# Scope_ArduinoCurveTracerV10.net
KiCad netlist of a schematic drawn in EAGLE
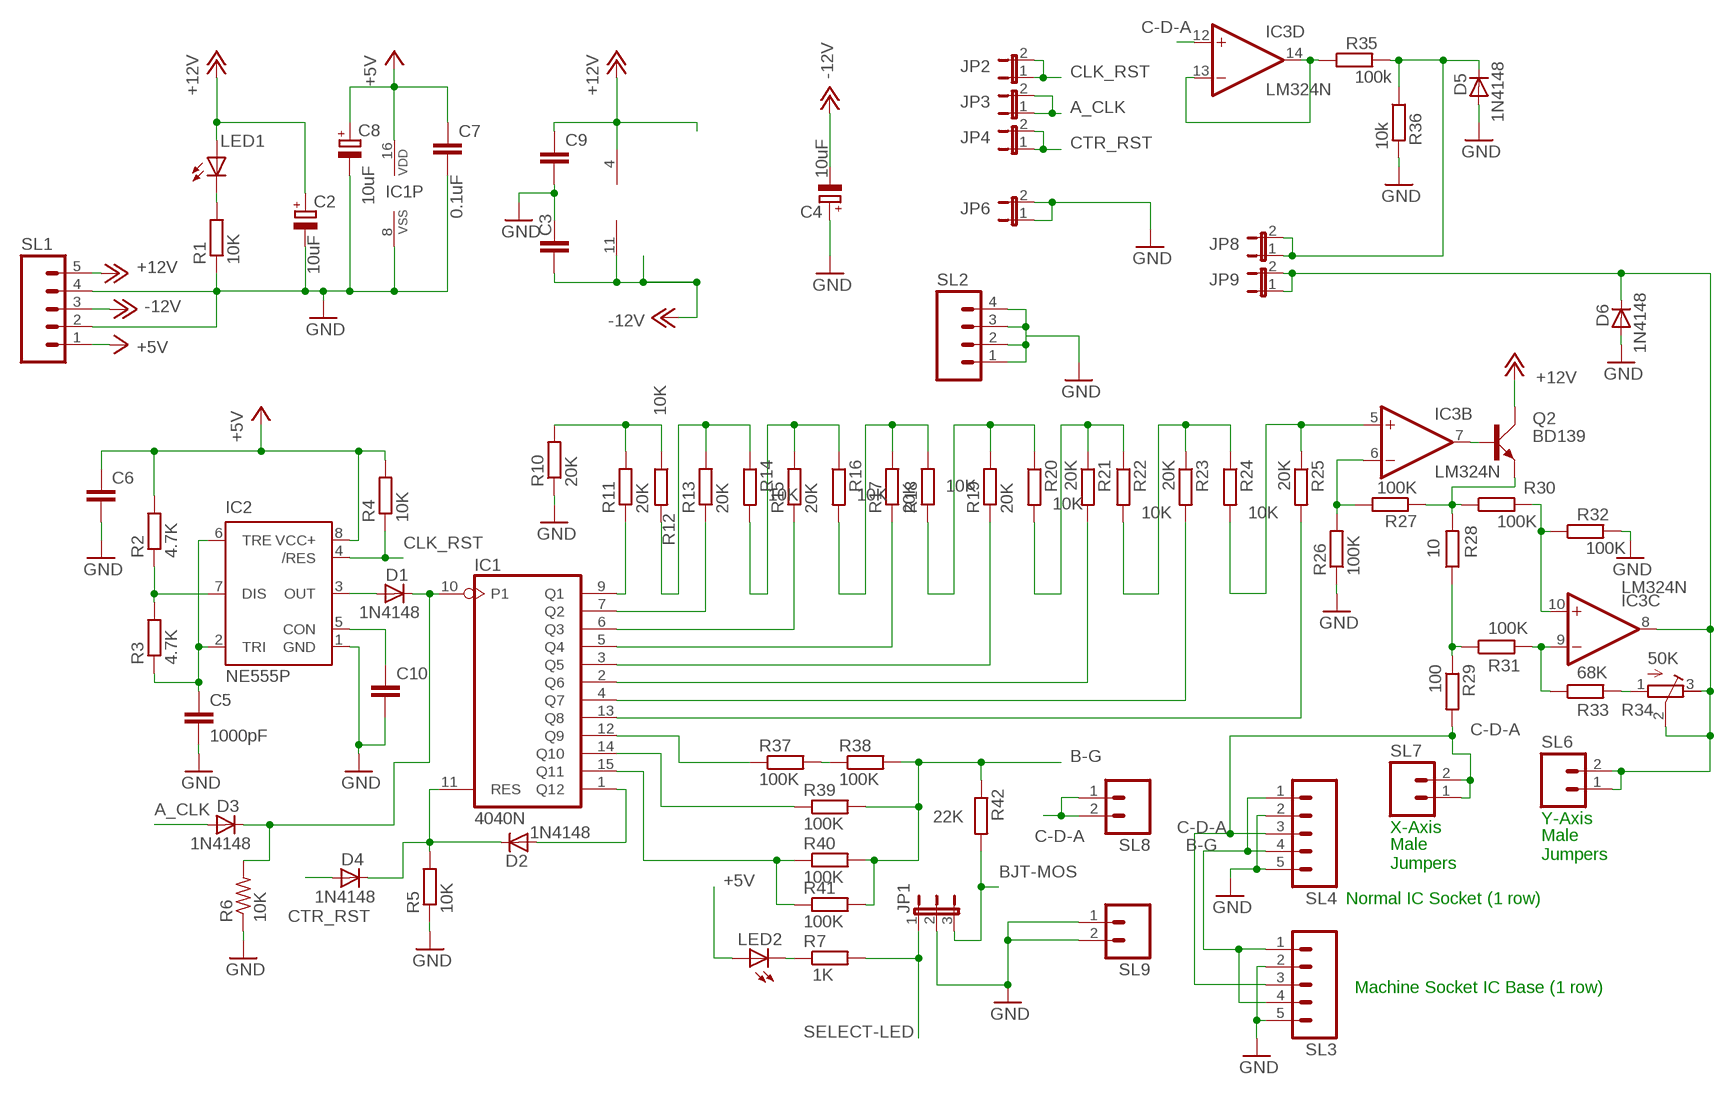
[diagram p0: schematic, sheet 1]

(export (version "E")
  (design (tool "Eeschema 10.0.6"))
  (components
    (comp (ref "C2")
      (value "10uF")
      (footprint "eagle-import:E2-5")
      (libsource (lib "eagle-import") (part "CPOL-EUE2-5"))
    )
    (comp (ref "C3")
      (value "0.1uF")
      (footprint "eagle-import:C025-024X044")
      (libsource (lib "eagle-import") (part "C-EU025-024X044"))
    )
    (comp (ref "C4")
      (value "10uF")
      (footprint "eagle-import:E2-5")
      (libsource (lib "eagle-import") (part "CPOL-EUE2-5"))
    )
    (comp (ref "C5")
      (value "1000pF")
      (footprint "eagle-import:C025-025X050")
      (libsource (lib "eagle-import") (part "C-EU025-025X050"))
    )
    (comp (ref "C6")
      (value "0.1uF")
      (footprint "eagle-import:C025-024X044")
      (libsource (lib "eagle-import") (part "C-EU025-024X044"))
    )
    (comp (ref "C7")
      (value "0.1uF")
      (footprint "eagle-import:C025-024X044")
      (libsource (lib "eagle-import") (part "C-EU025-024X044"))
    )
    (comp (ref "C8")
      (value "10uF")
      (footprint "eagle-import:E2-5")
      (libsource (lib "eagle-import") (part "CPOL-EUE2-5"))
    )
    (comp (ref "C9")
      (value "0.1uF")
      (footprint "eagle-import:C025-024X044")
      (libsource (lib "eagle-import") (part "C-EU025-024X044"))
    )
    (comp (ref "C10")
      (value "0.1uF")
      (footprint "eagle-import:C025-024X044")
      (libsource (lib "eagle-import") (part "C-EU025-024X044"))
    )
    (comp (ref "D1")
      (value "1N4148")
      (footprint "eagle-import:DO35-7")
      (libsource (lib "eagle-import") (part "1N4148DO35-7"))
    )
    (comp (ref "D2")
      (value "1N4148")
      (footprint "eagle-import:DO35-7")
      (libsource (lib "eagle-import") (part "1N4148DO35-7"))
    )
    (comp (ref "D3")
      (value "1N4148")
      (footprint "eagle-import:DO35-7")
      (libsource (lib "eagle-import") (part "1N4148DO35-7"))
    )
    (comp (ref "D4")
      (value "1N4148")
      (footprint "eagle-import:DO35-7")
      (libsource (lib "eagle-import") (part "1N4148DO35-7"))
    )
    (comp (ref "D5")
      (value "1N4148")
      (footprint "eagle-import:DO35-7")
      (libsource (lib "eagle-import") (part "1N4148DO35-7"))
    )
    (comp (ref "D6")
      (value "1N4148")
      (footprint "eagle-import:DO35-10")
      (libsource (lib "eagle-import") (part "1N4148DO35-10"))
    )
    (comp (ref "IC1")
      (value "4040N")
      (footprint "eagle-import:DIL16")
      (libsource (lib "eagle-import") (part "4040N"))
    )
    (comp (ref "IC2")
      (value "NE555P")
      (footprint "eagle-import:DIL-08")
      (fields (field (name "MF") "Arrow Electronics") (field (name "MPN") "NE555N"))
      (libsource (lib "eagle-import") (part "NE555P"))
    )
    (comp (ref "IC3")
      (value "LM324N")
      (footprint "eagle-import:DIL14")
      (libsource (lib "eagle-import") (part "LM324N"))
    )
    (comp (ref "JP1")
      (value "JP2E")
      (footprint "eagle-import:JP2")
      (libsource (lib "eagle-import") (part "JP2E"))
    )
    (comp (ref "JP2")
      (value "JP1E")
      (footprint "eagle-import:JP1")
      (libsource (lib "eagle-import") (part "JP1E"))
    )
    (comp (ref "JP3")
      (value "JP1E")
      (footprint "eagle-import:JP1")
      (libsource (lib "eagle-import") (part "JP1E"))
    )
    (comp (ref "JP4")
      (value "JP1E")
      (footprint "eagle-import:JP1")
      (libsource (lib "eagle-import") (part "JP1E"))
    )
    (comp (ref "JP6")
      (value "JP1E")
      (footprint "eagle-import:JP1")
      (libsource (lib "eagle-import") (part "JP1E"))
    )
    (comp (ref "JP8")
      (value "JP1E")
      (footprint "eagle-import:JP1")
      (libsource (lib "eagle-import") (part "JP1E"))
    )
    (comp (ref "JP9")
      (value "JP1E")
      (footprint "eagle-import:JP1")
      (libsource (lib "eagle-import") (part "JP1E"))
    )
    (comp (ref "LED1")
      (value "LED3MM")
      (footprint "eagle-import:LED3MM")
      (libsource (lib "eagle-import") (part "LED3MM"))
    )
    (comp (ref "LED2")
      (value "LED3MM")
      (footprint "eagle-import:LED3MM")
      (libsource (lib "eagle-import") (part "LED3MM"))
    )
    (comp (ref "Q2")
      (value "BD139")
      (footprint "eagle-import:TO126AV")
      (libsource (lib "eagle-import") (part "BD139"))
    )
    (comp (ref "R1")
      (value "10K")
      (footprint "eagle-import:0204_7")
      (libsource (lib "eagle-import") (part "R-EU_0204/7"))
    )
    (comp (ref "R2")
      (value "4.7K")
      (footprint "eagle-import:0204_7")
      (libsource (lib "eagle-import") (part "R-EU_0204/7"))
    )
    (comp (ref "R3")
      (value "4.7K")
      (footprint "eagle-import:0204_7")
      (libsource (lib "eagle-import") (part "R-EU_0204/7"))
    )
    (comp (ref "R4")
      (value "10K")
      (footprint "eagle-import:0204_7")
      (libsource (lib "eagle-import") (part "R-EU_0204/7"))
    )
    (comp (ref "R5")
      (value "10K")
      (footprint "eagle-import:0204_7")
      (libsource (lib "eagle-import") (part "R-EU_0204/7"))
    )
    (comp (ref "R6")
      (value "10K")
      (footprint "eagle-import:0204_7")
      (libsource (lib "eagle-import") (part "R-US_0204/7"))
    )
    (comp (ref "R7")
      (value "1K")
      (footprint "eagle-import:0204_7")
      (libsource (lib "eagle-import") (part "R-EU_0204/7"))
    )
    (comp (ref "R10")
      (value "20K")
      (footprint "eagle-import:0204_7")
      (libsource (lib "eagle-import") (part "R-EU_0204/7"))
    )
    (comp (ref "R11")
      (value "20K")
      (footprint "eagle-import:0204_7")
      (libsource (lib "eagle-import") (part "R-EU_0204/7"))
    )
    (comp (ref "R12")
      (value "10K")
      (footprint "eagle-import:0204_7")
      (libsource (lib "eagle-import") (part "R-EU_0204/7"))
    )
    (comp (ref "R13")
      (value "20K")
      (footprint "eagle-import:0204_7")
      (libsource (lib "eagle-import") (part "R-EU_0204/7"))
    )
    (comp (ref "R14")
      (value "10K")
      (footprint "eagle-import:0204_7")
      (libsource (lib "eagle-import") (part "R-EU_0204/7"))
    )
    (comp (ref "R15")
      (value "20K")
      (footprint "eagle-import:0204_7")
      (libsource (lib "eagle-import") (part "R-EU_0204/7"))
    )
    (comp (ref "R16")
      (value "10K")
      (footprint "eagle-import:0204_7")
      (libsource (lib "eagle-import") (part "R-EU_0204/7"))
    )
    (comp (ref "R17")
      (value "20K")
      (footprint "eagle-import:0204_7")
      (libsource (lib "eagle-import") (part "R-EU_0204/7"))
    )
    (comp (ref "R18")
      (value "10K")
      (footprint "eagle-import:0204_7")
      (libsource (lib "eagle-import") (part "R-EU_0204/7"))
    )
    (comp (ref "R19")
      (value "20K")
      (footprint "eagle-import:0204_7")
      (libsource (lib "eagle-import") (part "R-EU_0204/7"))
    )
    (comp (ref "R20")
      (value "10K")
      (footprint "eagle-import:0204_7")
      (libsource (lib "eagle-import") (part "R-EU_0204/7"))
    )
    (comp (ref "R21")
      (value "20K")
      (footprint "eagle-import:0204_7")
      (libsource (lib "eagle-import") (part "R-EU_0204/7"))
    )
    (comp (ref "R22")
      (value "10K")
      (footprint "eagle-import:0204_7")
      (libsource (lib "eagle-import") (part "R-EU_0204/7"))
    )
    (comp (ref "R23")
      (value "20K")
      (footprint "eagle-import:0204_7")
      (libsource (lib "eagle-import") (part "R-EU_0204/7"))
    )
    (comp (ref "R24")
      (value "10K")
      (footprint "eagle-import:0204_7")
      (libsource (lib "eagle-import") (part "R-EU_0204/7"))
    )
    (comp (ref "R25")
      (value "20K")
      (footprint "eagle-import:0204_7")
      (libsource (lib "eagle-import") (part "R-EU_0204/7"))
    )
    (comp (ref "R26")
      (value "100K")
      (footprint "eagle-import:0204_7")
      (libsource (lib "eagle-import") (part "R-EU_0204/7"))
    )
    (comp (ref "R27")
      (value "100K")
      (footprint "eagle-import:0204_7")
      (libsource (lib "eagle-import") (part "R-EU_0204/7"))
    )
    (comp (ref "R28")
      (value "10")
      (footprint "eagle-import:0207_10")
      (libsource (lib "eagle-import") (part "R-EU_0207/10"))
    )
    (comp (ref "R29")
      (value "100")
      (footprint "eagle-import:0309_12")
      (libsource (lib "eagle-import") (part "R-EU_0309/12"))
    )
    (comp (ref "R30")
      (value "100K")
      (footprint "eagle-import:0207_10")
      (libsource (lib "eagle-import") (part "R-EU_0207/10"))
    )
    (comp (ref "R31")
      (value "100K")
      (footprint "eagle-import:0204_7")
      (libsource (lib "eagle-import") (part "R-EU_0204/7"))
    )
    (comp (ref "R32")
      (value "100K")
      (footprint "eagle-import:0204_7")
      (libsource (lib "eagle-import") (part "R-EU_0204/7"))
    )
    (comp (ref "R33")
      (value "68K")
      (footprint "eagle-import:0204_7")
      (libsource (lib "eagle-import") (part "R-EU_0204/7"))
    )
    (comp (ref "R34")
      (value "50K")
      (footprint "eagle-import:RTRIM64W")
      (libsource (lib "eagle-import") (part "R-TRIMM64W"))
    )
    (comp (ref "R35")
      (value "100k")
      (footprint "eagle-import:0204_7")
      (libsource (lib "eagle-import") (part "R-EU_0204/7"))
    )
    (comp (ref "R36")
      (value "10k")
      (footprint "eagle-import:0204_7")
      (libsource (lib "eagle-import") (part "R-EU_0204/7"))
    )
    (comp (ref "R37")
      (value "100K")
      (footprint "eagle-import:0204_7")
      (libsource (lib "eagle-import") (part "R-EU_0204/7"))
    )
    (comp (ref "R38")
      (value "100K")
      (footprint "eagle-import:0204_7")
      (libsource (lib "eagle-import") (part "R-EU_0204/7"))
    )
    (comp (ref "R39")
      (value "100K")
      (footprint "eagle-import:0204_7")
      (libsource (lib "eagle-import") (part "R-EU_0204/7"))
    )
    (comp (ref "R40")
      (value "100K")
      (footprint "eagle-import:0204_7")
      (libsource (lib "eagle-import") (part "R-EU_0204/7"))
    )
    (comp (ref "R41")
      (value "100K")
      (footprint "eagle-import:0204_7")
      (libsource (lib "eagle-import") (part "R-EU_0204/7"))
    )
    (comp (ref "R42")
      (value "22K")
      (footprint "eagle-import:0204_7")
      (libsource (lib "eagle-import") (part "R-EU_0204/7"))
    )
    (comp (ref "SL1")
      (value "M05")
      (footprint "eagle-import:05P")
      (libsource (lib "eagle-import") (part "M05"))
    )
    (comp (ref "SL2")
      (value "M04")
      (footprint "eagle-import:04P")
      (libsource (lib "eagle-import") (part "M04"))
    )
    (comp (ref "SL3")
      (value "M05")
      (footprint "eagle-import:05P")
      (libsource (lib "eagle-import") (part "M05"))
    )
    (comp (ref "SL4")
      (value "M05")
      (footprint "eagle-import:05P")
      (libsource (lib "eagle-import") (part "M05"))
    )
    (comp (ref "SL6")
      (value "M02")
      (footprint "eagle-import:02P")
      (libsource (lib "eagle-import") (part "con-amp-quick_M02"))
    )
    (comp (ref "SL7")
      (value "M02")
      (footprint "eagle-import:02P")
      (libsource (lib "eagle-import") (part "M02"))
    )
    (comp (ref "SL8")
      (value "M02")
      (footprint "eagle-import:02P")
      (libsource (lib "eagle-import") (part "con-amp-quick_M02"))
    )
    (comp (ref "SL9")
      (value "M02")
      (footprint "eagle-import:02P")
      (libsource (lib "eagle-import") (part "con-amp-quick_M02"))
    )
  )
  (nets
    (net (code "1") (name "+5V") (class "Default")
      (node (ref "C6") (pin "1") (pinfunction "1_1") (pintype "passive"))
      (node (ref "C7") (pin "1") (pinfunction "1_1") (pintype "passive"))
      (node (ref "C8") (pin "+") (pinfunction "+_+") (pintype "passive"))
      (node (ref "IC1") (pin "16") (pinfunction "VDD_16") (pintype "power_in"))
      (node (ref "IC2") (pin "8") (pinfunction "VCC+_8") (pintype "power_in"))
      (node (ref "LED2") (pin "A") (pinfunction "A_A") (pintype "passive"))
      (node (ref "R2") (pin "2") (pinfunction "2_2") (pintype "passive"))
      (node (ref "R4") (pin "2") (pinfunction "2_2") (pintype "passive"))
      (node (ref "SL1") (pin "1") (pinfunction "1_1") (pintype "passive"))
    )
    (net (code "2") (name "+12V") (class "Default")
      (node (ref "C2") (pin "+") (pinfunction "+_+") (pintype "passive"))
      (node (ref "C9") (pin "1") (pinfunction "1_1") (pintype "passive"))
      (node (ref "IC3") (pin "4") (pinfunction "V+_4") (pintype "power_in"))
      (node (ref "LED1") (pin "A") (pinfunction "A_A") (pintype "passive"))
      (node (ref "Q2") (pin "C") (pinfunction "C_C") (pintype "passive"))
      (node (ref "SL1") (pin "5") (pinfunction "5_5") (pintype "passive"))
    )
    (net (code "3") (name "-12V") (class "Default")
      (node (ref "C3") (pin "2") (pinfunction "2_2") (pintype "passive"))
      (node (ref "C4") (pin "-") (pinfunction "-_-") (pintype "passive"))
      (node (ref "IC3") (pin "11") (pinfunction "V-_11") (pintype "power_in"))
      (node (ref "SL1") (pin "3") (pinfunction "3_3") (pintype "passive"))
    )
    (net (code "4") (name "/A_CLK") (class "Default")
      (node (ref "D3") (pin "A") (pinfunction "A_A") (pintype "passive"))
      (node (ref "JP3") (pin "1") (pinfunction "1_1") (pintype "passive"))
      (node (ref "JP3") (pin "2") (pinfunction "2_2") (pintype "passive"))
    )
    (net (code "5") (name "/B-G") (class "Default")
      (node (ref "R38") (pin "2") (pinfunction "2_2") (pintype "passive"))
      (node (ref "R39") (pin "2") (pinfunction "2_2") (pintype "passive"))
      (node (ref "R40") (pin "2") (pinfunction "2_2") (pintype "passive"))
      (node (ref "R41") (pin "2") (pinfunction "2_2") (pintype "passive"))
      (node (ref "R42") (pin "1") (pinfunction "1_1") (pintype "passive"))
      (node (ref "SL3") (pin "1") (pinfunction "1_1") (pintype "passive"))
      (node (ref "SL3") (pin "4") (pinfunction "4_4") (pintype "passive"))
      (node (ref "SL4") (pin "1") (pinfunction "1_1") (pintype "passive"))
      (node (ref "SL4") (pin "4") (pinfunction "4_4") (pintype "passive"))
    )
    (net (code "6") (name "/BJT-MOS") (class "Default")
      (node (ref "JP1") (pin "3") (pinfunction "3_3") (pintype "passive"))
      (node (ref "R42") (pin "2") (pinfunction "2_2") (pintype "passive"))
    )
    (net (code "7") (name "/C-D-A") (class "Default")
      (node (ref "IC3") (pin "12") (pinfunction "+IN_12") (pintype "input"))
      (node (ref "R29") (pin "2") (pinfunction "2_2") (pintype "passive"))
      (node (ref "SL3") (pin "3") (pinfunction "3_3") (pintype "passive"))
      (node (ref "SL4") (pin "3") (pinfunction "3_3") (pintype "passive"))
      (node (ref "SL7") (pin "1") (pinfunction "1_1") (pintype "passive"))
      (node (ref "SL7") (pin "2") (pinfunction "2_2") (pintype "passive"))
      (node (ref "SL8") (pin "1") (pinfunction "1_1") (pintype "passive"))
      (node (ref "SL8") (pin "2") (pinfunction "2_2") (pintype "passive"))
    )
    (net (code "8") (name "/CLK_RST") (class "Default")
      (node (ref "IC2") (pin "4") (pinfunction "/RES_4") (pintype "input"))
      (node (ref "JP2") (pin "1") (pinfunction "1_1") (pintype "passive"))
      (node (ref "JP2") (pin "2") (pinfunction "2_2") (pintype "passive"))
      (node (ref "R4") (pin "1") (pinfunction "1_1") (pintype "passive"))
    )
    (net (code "9") (name "/CTR_RST") (class "Default")
      (node (ref "D4") (pin "A") (pinfunction "A_A") (pintype "passive"))
      (node (ref "JP4") (pin "1") (pinfunction "1_1") (pintype "passive"))
      (node (ref "JP4") (pin "2") (pinfunction "2_2") (pintype "passive"))
    )
    (net (code "10") (name "/SELECT-LED") (class "Default")
      (node (ref "JP1") (pin "1") (pinfunction "1_1") (pintype "passive"))
      (node (ref "R7") (pin "2") (pinfunction "2_2") (pintype "passive"))
    )
    (net (code "11") (name "GND") (class "Default")
      (node (ref "C10") (pin "2") (pinfunction "2_2") (pintype "passive"))
      (node (ref "C2") (pin "-") (pinfunction "-_-") (pintype "passive"))
      (node (ref "C3") (pin "1") (pinfunction "1_1") (pintype "passive"))
      (node (ref "C4") (pin "+") (pinfunction "+_+") (pintype "passive"))
      (node (ref "C5") (pin "2") (pinfunction "2_2") (pintype "passive"))
      (node (ref "C6") (pin "2") (pinfunction "2_2") (pintype "passive"))
      (node (ref "C7") (pin "2") (pinfunction "2_2") (pintype "passive"))
      (node (ref "C8") (pin "-") (pinfunction "-_-") (pintype "passive"))
      (node (ref "C9") (pin "2") (pinfunction "2_2") (pintype "passive"))
      (node (ref "D5") (pin "A") (pinfunction "A_A") (pintype "passive"))
      (node (ref "D6") (pin "A") (pinfunction "A_A") (pintype "passive"))
      (node (ref "IC1") (pin "8") (pinfunction "VSS_8") (pintype "power_in"))
      (node (ref "IC2") (pin "1") (pinfunction "GND_1") (pintype "power_in"))
      (node (ref "JP1") (pin "2") (pinfunction "2_2") (pintype "passive"))
      (node (ref "JP6") (pin "1") (pinfunction "1_1") (pintype "passive"))
      (node (ref "JP6") (pin "2") (pinfunction "2_2") (pintype "passive"))
      (node (ref "R1") (pin "1") (pinfunction "1_1") (pintype "passive"))
      (node (ref "R10") (pin "1") (pinfunction "1_1") (pintype "passive"))
      (node (ref "R26") (pin "1") (pinfunction "1_1") (pintype "passive"))
      (node (ref "R32") (pin "2") (pinfunction "2_2") (pintype "passive"))
      (node (ref "R36") (pin "2") (pinfunction "2_2") (pintype "passive"))
      (node (ref "R5") (pin "1") (pinfunction "1_1") (pintype "passive"))
      (node (ref "R6") (pin "1") (pinfunction "1_1") (pintype "passive"))
      (node (ref "SL1") (pin "2") (pinfunction "2_2") (pintype "passive"))
      (node (ref "SL1") (pin "4") (pinfunction "4_4") (pintype "passive"))
      (node (ref "SL2") (pin "1") (pinfunction "1_1") (pintype "passive"))
      (node (ref "SL2") (pin "2") (pinfunction "2_2") (pintype "passive"))
      (node (ref "SL2") (pin "3") (pinfunction "3_3") (pintype "passive"))
      (node (ref "SL2") (pin "4") (pinfunction "4_4") (pintype "passive"))
      (node (ref "SL3") (pin "2") (pinfunction "2_2") (pintype "passive"))
      (node (ref "SL3") (pin "5") (pinfunction "5_5") (pintype "passive"))
      (node (ref "SL4") (pin "2") (pinfunction "2_2") (pintype "passive"))
      (node (ref "SL4") (pin "5") (pinfunction "5_5") (pintype "passive"))
      (node (ref "SL9") (pin "1") (pinfunction "1_1") (pintype "passive"))
      (node (ref "SL9") (pin "2") (pinfunction "2_2") (pintype "passive"))
    )
    (net (code "12") (name "Net-(D5-PadC)") (class "Default")
      (node (ref "D5") (pin "C") (pinfunction "C_C") (pintype "passive"))
      (node (ref "JP8") (pin "1") (pinfunction "1_1") (pintype "passive"))
      (node (ref "JP8") (pin "2") (pinfunction "2_2") (pintype "passive"))
      (node (ref "R35") (pin "2") (pinfunction "2_2") (pintype "passive"))
      (node (ref "R36") (pin "1") (pinfunction "1_1") (pintype "passive"))
    )
    (net (code "13") (name "Net-(IC1A-P1)") (class "Default")
      (node (ref "D1") (pin "C") (pinfunction "C_C") (pintype "passive"))
      (node (ref "D3") (pin "C") (pinfunction "C_C") (pintype "passive"))
      (node (ref "IC1") (pin "10") (pinfunction "P1_10") (pintype "input"))
      (node (ref "R6") (pin "2") (pinfunction "2_2") (pintype "passive"))
    )
    (net (code "14") (name "Net-(IC1A-Q1)") (class "Default")
      (node (ref "IC1") (pin "9") (pinfunction "Q1_9") (pintype "output"))
      (node (ref "R11") (pin "1") (pinfunction "1_1") (pintype "passive"))
    )
    (net (code "15") (name "Net-(IC1A-Q2)") (class "Default")
      (node (ref "IC1") (pin "7") (pinfunction "Q2_7") (pintype "output"))
      (node (ref "R13") (pin "1") (pinfunction "1_1") (pintype "passive"))
    )
    (net (code "16") (name "Net-(IC1A-Q3)") (class "Default")
      (node (ref "IC1") (pin "6") (pinfunction "Q3_6") (pintype "output"))
      (node (ref "R15") (pin "1") (pinfunction "1_1") (pintype "passive"))
    )
    (net (code "17") (name "Net-(IC1A-Q4)") (class "Default")
      (node (ref "IC1") (pin "5") (pinfunction "Q4_5") (pintype "output"))
      (node (ref "R17") (pin "1") (pinfunction "1_1") (pintype "passive"))
    )
    (net (code "18") (name "Net-(IC1A-Q5)") (class "Default")
      (node (ref "IC1") (pin "3") (pinfunction "Q5_3") (pintype "output"))
      (node (ref "R19") (pin "1") (pinfunction "1_1") (pintype "passive"))
    )
    (net (code "19") (name "Net-(IC1A-Q6)") (class "Default")
      (node (ref "IC1") (pin "2") (pinfunction "Q6_2") (pintype "output"))
      (node (ref "R21") (pin "2") (pinfunction "2_2") (pintype "passive"))
    )
    (net (code "20") (name "Net-(IC1A-Q7)") (class "Default")
      (node (ref "IC1") (pin "4") (pinfunction "Q7_4") (pintype "output"))
      (node (ref "R23") (pin "2") (pinfunction "2_2") (pintype "passive"))
    )
    (net (code "21") (name "Net-(IC1A-Q8)") (class "Default")
      (node (ref "IC1") (pin "13") (pinfunction "Q8_13") (pintype "output"))
      (node (ref "R25") (pin "2") (pinfunction "2_2") (pintype "passive"))
    )
    (net (code "22") (name "Net-(IC1A-Q9)") (class "Default")
      (node (ref "IC1") (pin "12") (pinfunction "Q9_12") (pintype "output"))
      (node (ref "R37") (pin "1") (pinfunction "1_1") (pintype "passive"))
    )
    (net (code "23") (name "Net-(IC1A-Q10)") (class "Default")
      (node (ref "IC1") (pin "14") (pinfunction "Q10_14") (pintype "output"))
      (node (ref "R39") (pin "1") (pinfunction "1_1") (pintype "passive"))
    )
    (net (code "24") (name "Net-(IC1A-Q11)") (class "Default")
      (node (ref "IC1") (pin "15") (pinfunction "Q11_15") (pintype "output"))
      (node (ref "R40") (pin "1") (pinfunction "1_1") (pintype "passive"))
      (node (ref "R41") (pin "1") (pinfunction "1_1") (pintype "passive"))
    )
    (net (code "25") (name "Net-(IC1A-Q12)") (class "Default")
      (node (ref "D2") (pin "A") (pinfunction "A_A") (pintype "passive"))
      (node (ref "IC1") (pin "1") (pinfunction "Q12_1") (pintype "output"))
    )
    (net (code "26") (name "Net-(IC1A-RES)") (class "Default")
      (node (ref "D2") (pin "C") (pinfunction "C_C") (pintype "passive"))
      (node (ref "D4") (pin "C") (pinfunction "C_C") (pintype "passive"))
      (node (ref "IC1") (pin "11") (pinfunction "RES_11") (pintype "input"))
      (node (ref "R5") (pin "2") (pinfunction "2_2") (pintype "passive"))
    )
    (net (code "27") (name "Net-(IC2-CON)") (class "Default")
      (node (ref "C10") (pin "1") (pinfunction "1_1") (pintype "passive"))
      (node (ref "IC2") (pin "5") (pinfunction "CON_5") (pintype "input"))
    )
    (net (code "28") (name "Net-(IC2-DIS)") (class "Default")
      (node (ref "IC2") (pin "7") (pinfunction "DIS_7") (pintype "input"))
      (node (ref "R2") (pin "1") (pinfunction "1_1") (pintype "passive"))
      (node (ref "R3") (pin "2") (pinfunction "2_2") (pintype "passive"))
    )
    (net (code "29") (name "Net-(IC2-OUT)") (class "Default")
      (node (ref "D1") (pin "A") (pinfunction "A_A") (pintype "passive"))
      (node (ref "IC2") (pin "3") (pinfunction "OUT_3") (pintype "output"))
    )
    (net (code "30") (name "Net-(IC2-TRE)") (class "Default")
      (node (ref "C5") (pin "1") (pinfunction "1_1") (pintype "passive"))
      (node (ref "IC2") (pin "2") (pinfunction "TRI_2") (pintype "input"))
      (node (ref "IC2") (pin "6") (pinfunction "TRE_6") (pintype "input"))
      (node (ref "R3") (pin "1") (pinfunction "1_1") (pintype "passive"))
    )
    (net (code "31") (name "Net-(IC3B-+IN)") (class "Default")
      (node (ref "IC3") (pin "5") (pinfunction "+IN_5") (pintype "input"))
      (node (ref "R24") (pin "2") (pinfunction "2_2") (pintype "passive"))
      (node (ref "R25") (pin "1") (pinfunction "1_1") (pintype "passive"))
    )
    (net (code "32") (name "Net-(IC3B--IN)") (class "Default")
      (node (ref "IC3") (pin "6") (pinfunction "-IN_6") (pintype "input"))
      (node (ref "R26") (pin "2") (pinfunction "2_2") (pintype "passive"))
      (node (ref "R27") (pin "2") (pinfunction "2_2") (pintype "passive"))
    )
    (net (code "33") (name "Net-(IC3B-OUT)") (class "Default")
      (node (ref "IC3") (pin "7") (pinfunction "OUT_7") (pintype "output"))
      (node (ref "Q2") (pin "B") (pinfunction "B_B") (pintype "passive"))
    )
    (net (code "34") (name "Net-(IC3C-+IN)") (class "Default")
      (node (ref "IC3") (pin "10") (pinfunction "+IN_10") (pintype "input"))
      (node (ref "R30") (pin "2") (pinfunction "2_2") (pintype "passive"))
      (node (ref "R32") (pin "1") (pinfunction "1_1") (pintype "passive"))
    )
    (net (code "35") (name "Net-(IC3C--IN)") (class "Default")
      (node (ref "IC3") (pin "9") (pinfunction "-IN_9") (pintype "input"))
      (node (ref "R31") (pin "2") (pinfunction "2_2") (pintype "passive"))
      (node (ref "R33") (pin "1") (pinfunction "1_1") (pintype "passive"))
    )
    (net (code "36") (name "Net-(IC3C-OUT)") (class "Default")
      (node (ref "D6") (pin "C") (pinfunction "C_C") (pintype "passive"))
      (node (ref "IC3") (pin "8") (pinfunction "OUT_8") (pintype "output"))
      (node (ref "JP9") (pin "1") (pinfunction "1_1") (pintype "passive"))
      (node (ref "JP9") (pin "2") (pinfunction "2_2") (pintype "passive"))
      (node (ref "R34") (pin "2") (pinfunction "S_2") (pintype "passive"))
      (node (ref "R34") (pin "3") (pinfunction "A_3") (pintype "passive"))
      (node (ref "SL6") (pin "1") (pinfunction "1_1") (pintype "passive"))
      (node (ref "SL6") (pin "2") (pinfunction "2_2") (pintype "passive"))
    )
    (net (code "37") (name "Net-(IC3D--IN)") (class "Default")
      (node (ref "IC3") (pin "13") (pinfunction "-IN_13") (pintype "input"))
      (node (ref "IC3") (pin "14") (pinfunction "OUT_14") (pintype "output"))
      (node (ref "R35") (pin "1") (pinfunction "1_1") (pintype "passive"))
    )
    (net (code "38") (name "Net-(LED1-C)") (class "Default")
      (node (ref "LED1") (pin "K") (pinfunction "C_K") (pintype "passive"))
      (node (ref "R1") (pin "2") (pinfunction "2_2") (pintype "passive"))
    )
    (net (code "39") (name "Net-(LED2-C)") (class "Default")
      (node (ref "LED2") (pin "K") (pinfunction "C_K") (pintype "passive"))
      (node (ref "R7") (pin "1") (pinfunction "1_1") (pintype "passive"))
    )
    (net (code "40") (name "Net-(Q2-PadE)") (class "Default")
      (node (ref "Q2") (pin "E") (pinfunction "E_E") (pintype "passive"))
      (node (ref "R27") (pin "1") (pinfunction "1_1") (pintype "passive"))
      (node (ref "R28") (pin "2") (pinfunction "2_2") (pintype "passive"))
      (node (ref "R30") (pin "1") (pinfunction "1_1") (pintype "passive"))
    )
    (net (code "41") (name "Net-(R10-Pad2)") (class "Default")
      (node (ref "R10") (pin "2") (pinfunction "2_2") (pintype "passive"))
      (node (ref "R11") (pin "2") (pinfunction "2_2") (pintype "passive"))
      (node (ref "R12") (pin "1") (pinfunction "1_1") (pintype "passive"))
    )
    (net (code "42") (name "Net-(R12-Pad2)") (class "Default")
      (node (ref "R12") (pin "2") (pinfunction "2_2") (pintype "passive"))
      (node (ref "R13") (pin "2") (pinfunction "2_2") (pintype "passive"))
      (node (ref "R14") (pin "1") (pinfunction "1_1") (pintype "passive"))
    )
    (net (code "43") (name "Net-(R14-Pad2)") (class "Default")
      (node (ref "R14") (pin "2") (pinfunction "2_2") (pintype "passive"))
      (node (ref "R15") (pin "2") (pinfunction "2_2") (pintype "passive"))
      (node (ref "R16") (pin "1") (pinfunction "1_1") (pintype "passive"))
    )
    (net (code "44") (name "Net-(R16-Pad2)") (class "Default")
      (node (ref "R16") (pin "2") (pinfunction "2_2") (pintype "passive"))
      (node (ref "R17") (pin "2") (pinfunction "2_2") (pintype "passive"))
      (node (ref "R18") (pin "2") (pinfunction "2_2") (pintype "passive"))
    )
    (net (code "45") (name "Net-(R18-Pad1)") (class "Default")
      (node (ref "R18") (pin "1") (pinfunction "1_1") (pintype "passive"))
      (node (ref "R19") (pin "2") (pinfunction "2_2") (pintype "passive"))
      (node (ref "R20") (pin "1") (pinfunction "1_1") (pintype "passive"))
    )
    (net (code "46") (name "Net-(R20-Pad2)") (class "Default")
      (node (ref "R20") (pin "2") (pinfunction "2_2") (pintype "passive"))
      (node (ref "R21") (pin "1") (pinfunction "1_1") (pintype "passive"))
      (node (ref "R22") (pin "1") (pinfunction "1_1") (pintype "passive"))
    )
    (net (code "47") (name "Net-(R22-Pad2)") (class "Default")
      (node (ref "R22") (pin "2") (pinfunction "2_2") (pintype "passive"))
      (node (ref "R23") (pin "1") (pinfunction "1_1") (pintype "passive"))
      (node (ref "R24") (pin "1") (pinfunction "1_1") (pintype "passive"))
    )
    (net (code "48") (name "Net-(R28-Pad1)") (class "Default")
      (node (ref "R28") (pin "1") (pinfunction "1_1") (pintype "passive"))
      (node (ref "R29") (pin "1") (pinfunction "1_1") (pintype "passive"))
      (node (ref "R31") (pin "1") (pinfunction "1_1") (pintype "passive"))
    )
    (net (code "49") (name "Net-(R34-E)") (class "Default")
      (node (ref "R33") (pin "2") (pinfunction "2_2") (pintype "passive"))
      (node (ref "R34") (pin "1") (pinfunction "E_1") (pintype "passive"))
    )
    (net (code "50") (name "Net-(R37-Pad2)") (class "Default")
      (node (ref "R37") (pin "2") (pinfunction "2_2") (pintype "passive"))
      (node (ref "R38") (pin "1") (pinfunction "1_1") (pintype "passive"))
    )
  )
)
